# main.net
KiCad netlist of a schematic drawn in EAGLE
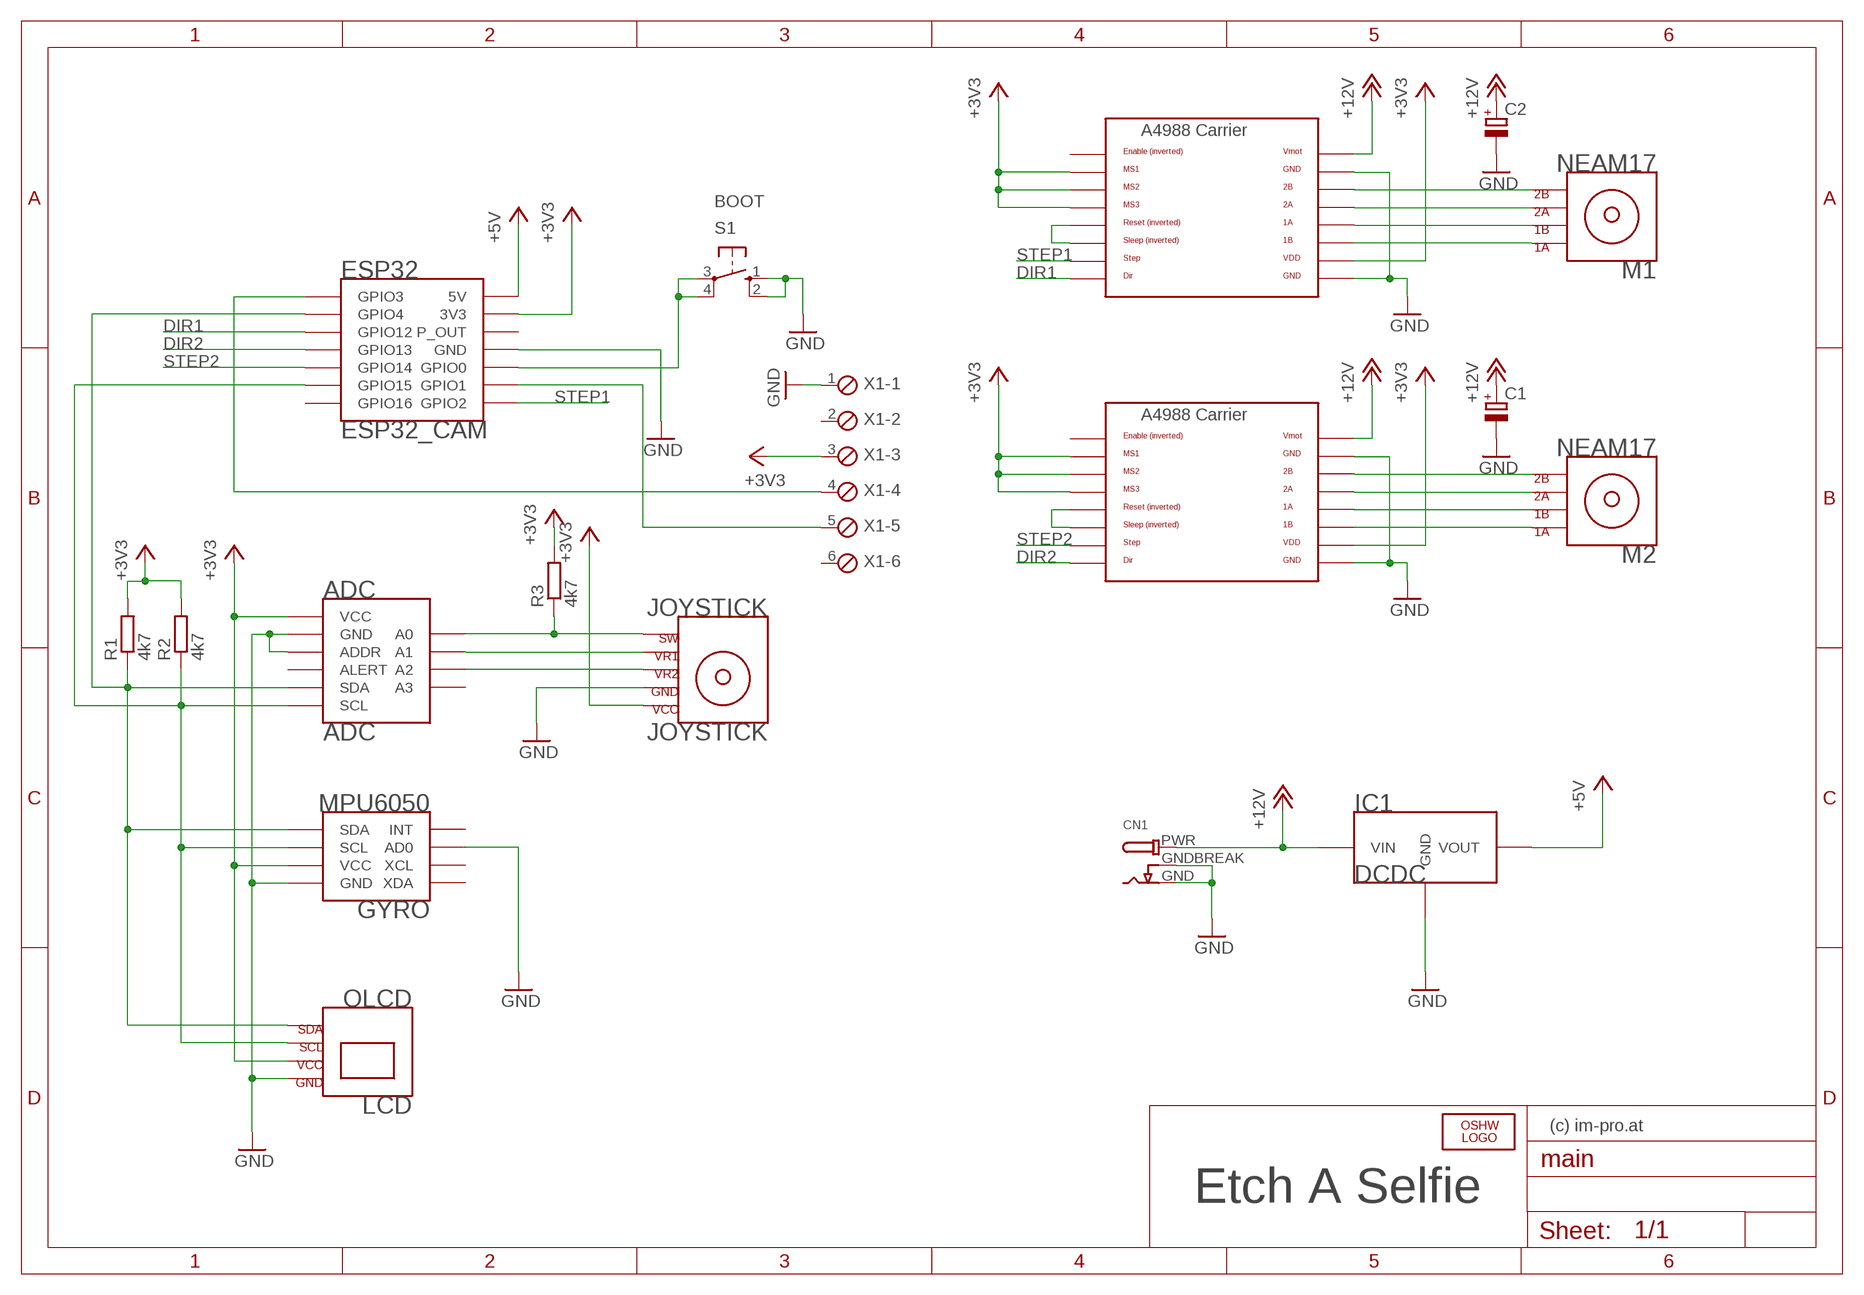
[diagram p0: schematic, sheet 1]

(export (version "E")
  (design (tool "Eeschema 10.0.6"))
  (components
    (comp (ref "ADC")
      (value "ADC")
      (footprint "eagle-import:ADC")
      (libsource (lib "eagle-import") (part "ADC"))
    )
    (comp (ref "C1")
      (value "CPOL-EUE2.5-6")
      (footprint "eagle-import:E2,5-6")
      (libsource (lib "eagle-import") (part "CPOL-EUE2.5-6"))
    )
    (comp (ref "C2")
      (value "CPOL-EUE2.5-6")
      (footprint "eagle-import:E2,5-6")
      (libsource (lib "eagle-import") (part "CPOL-EUE2.5-6"))
    )
    (comp (ref "CN1")
      (value "DCBARRELPTH")
      (footprint "eagle-import:DCJACK_2MM_PTH")
      (libsource (lib "eagle-import") (part "DCBARRELPTH"))
    )
    (comp (ref "ESP32")
      (value "ESP32_CAM")
      (footprint "eagle-import:ESP32_CAM")
      (libsource (lib "eagle-import") (part "ESP32_CAM"))
    )
    (comp (ref "GYRO")
      (value "MPU6050")
      (footprint "eagle-import:MPU6050")
      (libsource (lib "eagle-import") (part "MPU6050"))
    )
    (comp (ref "IC1")
      (value "DCDC")
      (footprint "eagle-import:DCDC")
      (libsource (lib "eagle-import") (part "DCDC"))
    )
    (comp (ref "IC2")
      (value "A4988BREAKOUT")
      (footprint "eagle-import:A4988BREAKOUT")
      (libsource (lib "eagle-import") (part "A4988BREAKOUT"))
    )
    (comp (ref "IC3")
      (value "A4988BREAKOUT")
      (footprint "eagle-import:A4988BREAKOUT")
      (libsource (lib "eagle-import") (part "A4988BREAKOUT"))
    )
    (comp (ref "JOYSTICK")
      (value "JOYSTICK")
      (footprint "eagle-import:JOYSTICK")
      (libsource (lib "eagle-import") (part "JOYSTICK"))
    )
    (comp (ref "LCD")
      (value "OLCD")
      (footprint "eagle-import:OLCD")
      (libsource (lib "eagle-import") (part "OLCD"))
    )
    (comp (ref "LOGO1")
      (value "OHW-LOGO_OSHW_LOGO_FILLX0350-NT")
      (footprint "eagle-import:OHW-LOGO_OSHW_FILLX350_NOTEXT")
      (libsource (lib "eagle-import") (part "OHW-LOGO_OSHW_LOGO_FILLX0350-NT"))
    )
    (comp (ref "M1")
      (value "NEAM17")
      (footprint "eagle-import:NEMA17")
      (libsource (lib "eagle-import") (part "NEAM17"))
    )
    (comp (ref "M2")
      (value "NEAM17")
      (footprint "eagle-import:NEMA17")
      (libsource (lib "eagle-import") (part "NEAM17"))
    )
    (comp (ref "R1")
      (value "4k7")
      (footprint "eagle-import:0207_10")
      (libsource (lib "eagle-import") (part "R-EU_0207/10"))
    )
    (comp (ref "R2")
      (value "4k7")
      (footprint "eagle-import:0207_10")
      (libsource (lib "eagle-import") (part "R-EU_0207/10"))
    )
    (comp (ref "R3")
      (value "4k7")
      (footprint "eagle-import:0207_10")
      (libsource (lib "eagle-import") (part "R-EU_0207/10"))
    )
    (comp (ref "S1")
      (value "10-XX")
      (footprint "eagle-import:B3F-10XX")
      (fields (field (name "MPN") "B3F-1000"))
      (libsource (lib "eagle-import") (part "10-XX"))
    )
    (comp (ref "X1")
      (value "MPT6")
      (footprint "eagle-import:6POL254")
      (libsource (lib "eagle-import") (part "MPT6"))
    )
  )
  (nets
    (net (code "1") (name "+3V3") (class "Default")
      (node (ref "ADC") (pin "VCC") (pinfunction "VCC_VCC") (pintype "bidirectional"))
      (node (ref "ESP32") (pin "3V3") (pinfunction "3V3_3V3") (pintype "bidirectional"))
      (node (ref "GYRO") (pin "VCC") (pinfunction "VCC_VCC") (pintype "bidirectional"))
      (node (ref "IC2") (pin "MS1") (pinfunction "MS1_MS1") (pintype "input"))
      (node (ref "IC2") (pin "MS2") (pinfunction "MS2_MS2") (pintype "input"))
      (node (ref "IC2") (pin "MS3") (pinfunction "MS3_MS3") (pintype "input"))
      (node (ref "IC2") (pin "VDD") (pinfunction "VDD_VDD") (pintype "power_in"))
      (node (ref "IC3") (pin "MS1") (pinfunction "MS1_MS1") (pintype "input"))
      (node (ref "IC3") (pin "MS2") (pinfunction "MS2_MS2") (pintype "input"))
      (node (ref "IC3") (pin "MS3") (pinfunction "MS3_MS3") (pintype "input"))
      (node (ref "IC3") (pin "VDD") (pinfunction "VDD_VDD") (pintype "power_in"))
      (node (ref "JOYSTICK") (pin "VCC") (pinfunction "VCC_VCC") (pintype "bidirectional"))
      (node (ref "LCD") (pin "VCC") (pinfunction "VCC_VCC") (pintype "bidirectional"))
      (node (ref "R1") (pin "2") (pinfunction "2_2") (pintype "passive"))
      (node (ref "R2") (pin "2") (pinfunction "2_2") (pintype "passive"))
      (node (ref "R3") (pin "2") (pinfunction "2_2") (pintype "passive"))
      (node (ref "X1") (pin "3") (pinfunction "1_3") (pintype "passive"))
    )
    (net (code "2") (name "+5V") (class "Default")
      (node (ref "ESP32") (pin "5V") (pinfunction "5V_5V") (pintype "bidirectional"))
      (node (ref "IC1") (pin "VOUT") (pinfunction "VOUT_VOUT") (pintype "power_in"))
    )
    (net (code "3") (name "+12V") (class "Default")
      (node (ref "C1") (pin "+") (pinfunction "+_+") (pintype "passive"))
      (node (ref "C2") (pin "+") (pinfunction "+_+") (pintype "passive"))
      (node (ref "CN1") (pin "PWR") (pinfunction "PWR_PWR") (pintype "power_in"))
      (node (ref "IC1") (pin "VIN") (pinfunction "VIN_VIN") (pintype "power_in"))
      (node (ref "IC2") (pin "VMOT") (pinfunction "VMOT_VMOT") (pintype "power_in"))
      (node (ref "IC3") (pin "VMOT") (pinfunction "VMOT_VMOT") (pintype "power_in"))
    )
    (net (code "4") (name "/DIR1") (class "Default")
      (node (ref "ESP32") (pin "GPIO12") (pinfunction "GPIO12_GPIO12") (pintype "bidirectional"))
      (node (ref "IC2") (pin "DIR") (pinfunction "DIR_DIR") (pintype "input"))
    )
    (net (code "5") (name "/DIR2") (class "Default")
      (node (ref "ESP32") (pin "GPIO13") (pinfunction "GPIO13_GPIO13") (pintype "bidirectional"))
      (node (ref "IC3") (pin "DIR") (pinfunction "DIR_DIR") (pintype "input"))
    )
    (net (code "6") (name "/STEP1") (class "Default")
      (node (ref "ESP32") (pin "GPIO2") (pinfunction "GPIO2_GPIO2") (pintype "bidirectional"))
      (node (ref "IC2") (pin "STEP") (pinfunction "STEP_STEP") (pintype "input"))
    )
    (net (code "7") (name "/STEP2") (class "Default")
      (node (ref "ESP32") (pin "GPIO14") (pinfunction "GPIO14_GPIO14") (pintype "bidirectional"))
      (node (ref "IC3") (pin "STEP") (pinfunction "STEP_STEP") (pintype "input"))
    )
    (net (code "8") (name "GND") (class "Default")
      (node (ref "ADC") (pin "ADDR") (pinfunction "ADDR_ADDR") (pintype "bidirectional"))
      (node (ref "ADC") (pin "GND") (pinfunction "GND_GND") (pintype "bidirectional"))
      (node (ref "C1") (pin "-") (pinfunction "-_-") (pintype "passive"))
      (node (ref "C2") (pin "-") (pinfunction "-_-") (pintype "passive"))
      (node (ref "CN1") (pin "GND") (pinfunction "GND_GND") (pintype "power_in"))
      (node (ref "CN1") (pin "GNDBREAK") (pinfunction "GNDBREAK_GNDBREAK") (pintype "power_in"))
      (node (ref "ESP32") (pin "GND1") (pinfunction "GND_GND1") (pintype "bidirectional"))
      (node (ref "ESP32") (pin "GND2") (pinfunction "GND_GND2") (pintype "bidirectional"))
      (node (ref "ESP32") (pin "GND3") (pinfunction "GND_GND3") (pintype "bidirectional"))
      (node (ref "GYRO") (pin "AD0") (pinfunction "AD0_AD0") (pintype "bidirectional"))
      (node (ref "GYRO") (pin "GND") (pinfunction "GND_GND") (pintype "bidirectional"))
      (node (ref "IC1") (pin "GND1") (pinfunction "GND_GND1") (pintype "power_in"))
      (node (ref "IC1") (pin "GND2") (pinfunction "GND_GND2") (pintype "power_in"))
      (node (ref "IC2") (pin "GND") (pinfunction "GND_GND") (pintype "power_in"))
      (node (ref "IC2") (pin "GND@0") (pinfunction "GND_GND@0") (pintype "power_in"))
      (node (ref "IC3") (pin "GND") (pinfunction "GND_GND") (pintype "power_in"))
      (node (ref "IC3") (pin "GND@0") (pinfunction "GND_GND@0") (pintype "power_in"))
      (node (ref "JOYSTICK") (pin "GND") (pinfunction "GND_GND") (pintype "bidirectional"))
      (node (ref "LCD") (pin "GND") (pinfunction "GND_GND") (pintype "bidirectional"))
      (node (ref "S1") (pin "1") (pinfunction "S_1") (pintype "passive"))
      (node (ref "S1") (pin "2") (pinfunction "S1_2") (pintype "passive"))
      (node (ref "X1") (pin "1") (pinfunction "1_1") (pintype "passive"))
    )
    (net (code "9") (name "Net-(ADC-PadA0)") (class "Default")
      (node (ref "ADC") (pin "A0") (pinfunction "A0_A0") (pintype "bidirectional"))
      (node (ref "JOYSTICK") (pin "SW") (pinfunction "SW_SW") (pintype "bidirectional"))
      (node (ref "R3") (pin "1") (pinfunction "1_1") (pintype "passive"))
    )
    (net (code "10") (name "Net-(ADC-PadA1)") (class "Default")
      (node (ref "ADC") (pin "A1") (pinfunction "A1_A1") (pintype "bidirectional"))
      (node (ref "JOYSTICK") (pin "VR1") (pinfunction "VR1_VR1") (pintype "bidirectional"))
    )
    (net (code "11") (name "Net-(ADC-PadA2)") (class "Default")
      (node (ref "ADC") (pin "A2") (pinfunction "A2_A2") (pintype "bidirectional"))
      (node (ref "JOYSTICK") (pin "VR2") (pinfunction "VR2_VR2") (pintype "bidirectional"))
    )
    (net (code "12") (name "Net-(ADC-PadSCL)") (class "Default")
      (node (ref "ADC") (pin "SCL") (pinfunction "SCL_SCL") (pintype "bidirectional"))
      (node (ref "ESP32") (pin "GPIO15") (pinfunction "GPIO15_GPIO15") (pintype "bidirectional"))
      (node (ref "GYRO") (pin "SCL") (pinfunction "SCL_SCL") (pintype "bidirectional"))
      (node (ref "LCD") (pin "SCL") (pinfunction "SCL_SCL") (pintype "bidirectional"))
      (node (ref "R2") (pin "1") (pinfunction "1_1") (pintype "passive"))
    )
    (net (code "13") (name "Net-(ADC-PadSDA)") (class "Default")
      (node (ref "ADC") (pin "SDA") (pinfunction "SDA_SDA") (pintype "bidirectional"))
      (node (ref "ESP32") (pin "GPIO4") (pinfunction "GPIO4_GPIO4") (pintype "bidirectional"))
      (node (ref "GYRO") (pin "SDA") (pinfunction "SDA_SDA") (pintype "bidirectional"))
      (node (ref "LCD") (pin "SDA") (pinfunction "SDA_SDA") (pintype "bidirectional"))
      (node (ref "R1") (pin "1") (pinfunction "1_1") (pintype "passive"))
    )
    (net (code "14") (name "Net-(IC2-Pad1A)") (class "Default")
      (node (ref "IC2") (pin "1A") (pinfunction "1A_1A") (pintype "output"))
      (node (ref "M1") (pin "1B") (pinfunction "1B_1B") (pintype "bidirectional"))
    )
    (net (code "15") (name "Net-(IC2-Pad1B)") (class "Default")
      (node (ref "IC2") (pin "1B") (pinfunction "1B_1B") (pintype "output"))
      (node (ref "M1") (pin "1A") (pinfunction "1A_1A") (pintype "bidirectional"))
    )
    (net (code "16") (name "Net-(IC2-Pad2A)") (class "Default")
      (node (ref "IC2") (pin "2A") (pinfunction "2A_2A") (pintype "output"))
      (node (ref "M1") (pin "2A") (pinfunction "2A_2A") (pintype "bidirectional"))
    )
    (net (code "17") (name "Net-(IC2-Pad2B)") (class "Default")
      (node (ref "IC2") (pin "2B") (pinfunction "2B_2B") (pintype "output"))
      (node (ref "M1") (pin "2B") (pinfunction "2B_2B") (pintype "bidirectional"))
    )
    (net (code "18") (name "Net-(IC2-SLEEP)") (class "Default")
      (node (ref "IC2") (pin "RST") (pinfunction "RST_RST") (pintype "input"))
      (node (ref "IC2") (pin "SLP") (pinfunction "SLEEP_SLP") (pintype "input"))
    )
    (net (code "19") (name "Net-(IC3-Pad1A)") (class "Default")
      (node (ref "IC3") (pin "1A") (pinfunction "1A_1A") (pintype "output"))
      (node (ref "M2") (pin "1B") (pinfunction "1B_1B") (pintype "bidirectional"))
    )
    (net (code "20") (name "Net-(IC3-Pad1B)") (class "Default")
      (node (ref "IC3") (pin "1B") (pinfunction "1B_1B") (pintype "output"))
      (node (ref "M2") (pin "1A") (pinfunction "1A_1A") (pintype "bidirectional"))
    )
    (net (code "21") (name "Net-(IC3-Pad2A)") (class "Default")
      (node (ref "IC3") (pin "2A") (pinfunction "2A_2A") (pintype "output"))
      (node (ref "M2") (pin "2A") (pinfunction "2A_2A") (pintype "bidirectional"))
    )
    (net (code "22") (name "Net-(IC3-Pad2B)") (class "Default")
      (node (ref "IC3") (pin "2B") (pinfunction "2B_2B") (pintype "output"))
      (node (ref "M2") (pin "2B") (pinfunction "2B_2B") (pintype "bidirectional"))
    )
    (net (code "23") (name "Net-(IC3-SLEEP)") (class "Default")
      (node (ref "IC3") (pin "RST") (pinfunction "RST_RST") (pintype "input"))
      (node (ref "IC3") (pin "SLP") (pinfunction "SLEEP_SLP") (pintype "input"))
    )
    (net (code "24") (name "Net-(S1-P)") (class "Default")
      (node (ref "ESP32") (pin "GPIO0") (pinfunction "GPIO0_GPIO0") (pintype "bidirectional"))
      (node (ref "S1") (pin "3") (pinfunction "P_3") (pintype "passive"))
      (node (ref "S1") (pin "4") (pinfunction "P1_4") (pintype "passive"))
    )
    (net (code "25") (name "Net-(X1D-1)") (class "Default")
      (node (ref "ESP32") (pin "GPIO3") (pinfunction "GPIO3_GPIO3") (pintype "bidirectional"))
      (node (ref "X1") (pin "4") (pinfunction "1_4") (pintype "passive"))
    )
    (net (code "26") (name "Net-(X1E-1)") (class "Default")
      (node (ref "ESP32") (pin "GPIO1") (pinfunction "GPIO1_GPIO1") (pintype "bidirectional"))
      (node (ref "X1") (pin "5") (pinfunction "1_5") (pintype "passive"))
    )
    (net (code "27") (name "unconnected-(ADC-PadA3)") (class "Default")
      (node (ref "ADC") (pin "A3") (pinfunction "A3_A3") (pintype "bidirectional"))
    )
    (net (code "28") (name "unconnected-(ADC-PadALERT)") (class "Default")
      (node (ref "ADC") (pin "ALERT") (pinfunction "ALERT_ALERT") (pintype "bidirectional"))
    )
    (net (code "29") (name "unconnected-(ESP32-PadGPIO16)") (class "Default")
      (node (ref "ESP32") (pin "GPIO16") (pinfunction "GPIO16_GPIO16") (pintype "bidirectional"))
    )
    (net (code "30") (name "unconnected-(ESP32-PadP_OUT)") (class "Default")
      (node (ref "ESP32") (pin "P_OUT") (pinfunction "P_OUT_P_OUT") (pintype "bidirectional"))
    )
    (net (code "31") (name "unconnected-(GYRO-PadINT)") (class "Default")
      (node (ref "GYRO") (pin "INT") (pinfunction "INT_INT") (pintype "bidirectional"))
    )
    (net (code "32") (name "unconnected-(GYRO-PadXCL)") (class "Default")
      (node (ref "GYRO") (pin "XCL") (pinfunction "XCL_XCL") (pintype "bidirectional"))
    )
    (net (code "33") (name "unconnected-(GYRO-PadXDA)") (class "Default")
      (node (ref "GYRO") (pin "XDA") (pinfunction "XDA_XDA") (pintype "bidirectional"))
    )
    (net (code "34") (name "unconnected-(IC2-PadEN)") (class "Default")
      (node (ref "IC2") (pin "EN") (pinfunction "EN_EN") (pintype "input"))
    )
    (net (code "35") (name "unconnected-(IC3-PadEN)") (class "Default")
      (node (ref "IC3") (pin "EN") (pinfunction "EN_EN") (pintype "input"))
    )
    (net (code "36") (name "unconnected-(X1B-1-Pad2)") (class "Default")
      (node (ref "X1") (pin "2") (pinfunction "1_2") (pintype "passive"))
    )
    (net (code "37") (name "unconnected-(X1F-1-Pad6)") (class "Default")
      (node (ref "X1") (pin "6") (pinfunction "1_6") (pintype "passive"))
    )
  )
)
